# AMP_N2.net
KiCad netlist of a schematic drawn in Altium Designer
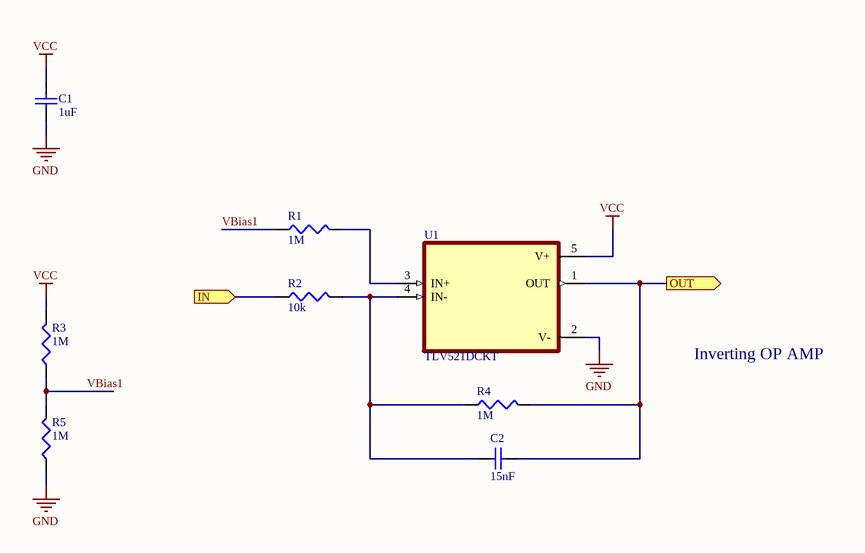
[diagram p0: AMP_N2.schDoc]

(export (version "E")
  (design (tool "Eeschema 10.0.6"))
  (components
    (comp (ref "C1")
      (value "1uF")
      (footprint "SMD-0603")
      (description "Ceramic Capacitor 0603")
      (libsource (lib "LCR") (part "CAP0603"))
    )
    (comp (ref "C2")
      (value "15nF")
      (footprint "SMD-0603")
      (description "Ceramic Capacitor 0603")
      (libsource (lib "LCR") (part "CAP0603"))
    )
    (comp (ref "R1")
      (value "1M")
      (footprint "SMD-0603")
      (description "Resistor-0603")
      (libsource (lib "LCR") (part "RES0603"))
    )
    (comp (ref "R2")
      (value "10k")
      (footprint "SMD-0603")
      (description "Resistor-0603")
      (libsource (lib "LCR") (part "RES0603"))
    )
    (comp (ref "R3")
      (value "1M")
      (footprint "SMD-0603")
      (description "Resistor-0603")
      (libsource (lib "LCR") (part "RES0603"))
    )
    (comp (ref "R4")
      (value "1M")
      (footprint "SMD-0603")
      (description "Resistor-0603")
      (libsource (lib "LCR") (part "RES0603"))
    )
    (comp (ref "R5")
      (value "1M")
      (footprint "SMD-0603")
      (description "Resistor-0603")
      (libsource (lib "LCR") (part "RES0603"))
    )
    (comp (ref "U1")
      (value "TLV521DCKT")
      (footprint "TLV521-SOT-5N")
      (fields (field (name "MF") "Texas Instruments"))
      (libsource (lib "op_amp") (part "TLV521DCKT"))
    )
  )
  (nets
    (net (code "1") (name "/IN") (class "Default")
      (node (ref "R2") (pin "1") (pinfunction "1_1") (pintype "passive"))
    )
    (net (code "2") (name "/OUT") (class "Default")
      (node (ref "C2") (pin "2") (pinfunction "2_2") (pintype "passive"))
      (node (ref "R4") (pin "2") (pinfunction "2_2") (pintype "passive"))
      (node (ref "U1") (pin "1") (pinfunction "OUT_1") (pintype "output"))
    )
    (net (code "3") (name "/VBias1") (class "Default")
      (node (ref "R1") (pin "1") (pinfunction "1_1") (pintype "passive"))
      (node (ref "R3") (pin "1") (pinfunction "1_1") (pintype "passive"))
      (node (ref "R5") (pin "2") (pinfunction "2_2") (pintype "passive"))
    )
    (net (code "4") (name "GND") (class "Default")
      (node (ref "C1") (pin "1") (pinfunction "1_1") (pintype "passive"))
      (node (ref "R5") (pin "1") (pinfunction "1_1") (pintype "passive"))
      (node (ref "U1") (pin "2") (pinfunction "V-_2") (pintype "power_in"))
    )
    (net (code "5") (name "Net-(U1-IN+)") (class "Default")
      (node (ref "R1") (pin "2") (pinfunction "2_2") (pintype "passive"))
      (node (ref "U1") (pin "3") (pinfunction "IN+_3") (pintype "input"))
    )
    (net (code "6") (name "Net-(U1-IN-)") (class "Default")
      (node (ref "C2") (pin "1") (pinfunction "1_1") (pintype "passive"))
      (node (ref "R2") (pin "2") (pinfunction "2_2") (pintype "passive"))
      (node (ref "R4") (pin "1") (pinfunction "1_1") (pintype "passive"))
      (node (ref "U1") (pin "4") (pinfunction "IN-_4") (pintype "input"))
    )
    (net (code "7") (name "VCC") (class "Default")
      (node (ref "C1") (pin "2") (pinfunction "2_2") (pintype "passive"))
      (node (ref "R3") (pin "2") (pinfunction "2_2") (pintype "passive"))
      (node (ref "U1") (pin "5") (pinfunction "V+_5") (pintype "power_in"))
    )
  )
)
